# RemoteCar_V1_0.net
KiCad netlist of a schematic drawn in Altium Designer
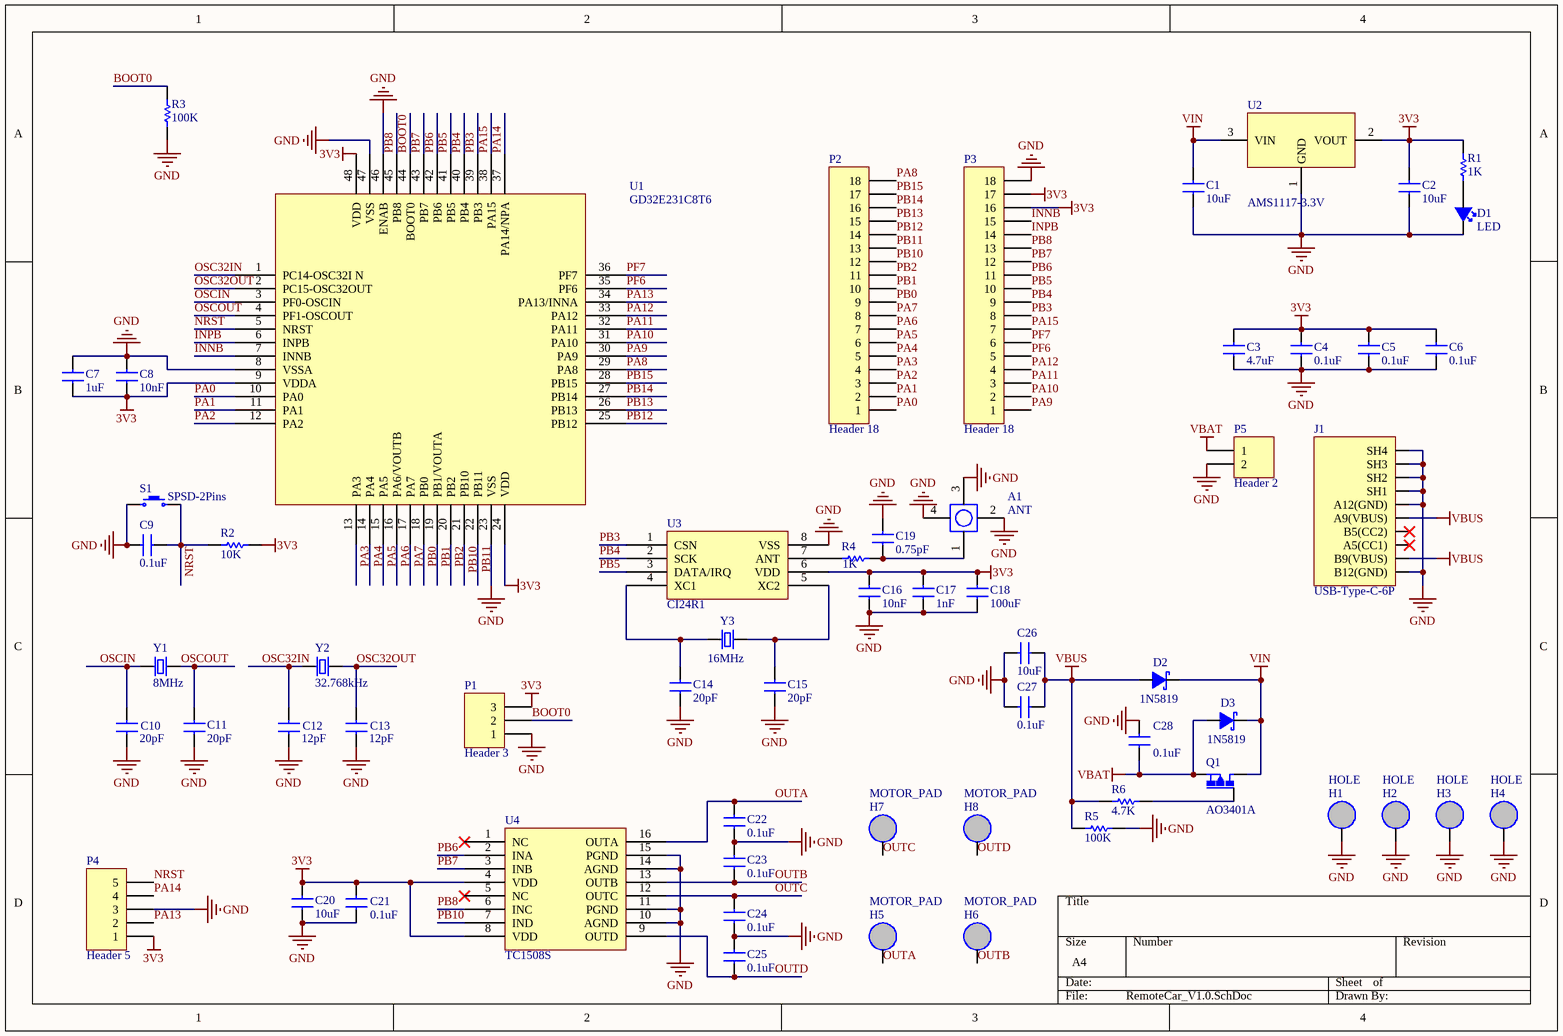
[diagram p0: RemoteCar_V1.0.SchDoc]

(export (version "E")
  (design (tool "Eeschema 10.0.6"))
  (components
    (comp (ref "A1")
      (value "ANT")
      (footprint "RemoteCar_V1.0:IPEX1")
      (libsource (lib "RemoteCar_V1.0") (part "ANT"))
    )
    (comp (ref "C1") (value "10uF") (footprint "CAP-0603") (libsource (lib "GeneralLib") (part "Capacitor")))
    (comp (ref "C2") (value "10uF") (footprint "CAP-0603") (libsource (lib "GeneralLib") (part "Capacitor")))
    (comp (ref "C3") (value "4.7uF") (footprint "CAP-0603") (libsource (lib "GeneralLib") (part "Capacitor")))
    (comp (ref "C4") (value "0.1uF") (footprint "CAP-0402") (libsource (lib "GeneralLib") (part "Capacitor")))
    (comp (ref "C5") (value "0.1uF") (footprint "CAP-0402") (libsource (lib "GeneralLib") (part "Capacitor")))
    (comp (ref "C6") (value "0.1uF") (footprint "CAP-0402") (libsource (lib "GeneralLib") (part "Capacitor")))
    (comp (ref "C7") (value "1uF") (footprint "CAP-0402") (libsource (lib "GeneralLib") (part "Capacitor")))
    (comp (ref "C8") (value "10nF") (footprint "CAP-0402") (libsource (lib "GeneralLib") (part "Capacitor")))
    (comp (ref "C9") (value "0.1uF") (footprint "CAP-0402") (libsource (lib "GeneralLib") (part "Capacitor")))
    (comp (ref "C10") (value "20pF") (footprint "CAP-0603") (libsource (lib "GeneralLib") (part "Capacitor")))
    (comp (ref "C11") (value "20pF") (footprint "CAP-0603") (libsource (lib "GeneralLib") (part "Capacitor")))
    (comp (ref "C12") (value "12pF") (footprint "CAP-0603") (libsource (lib "GeneralLib") (part "Capacitor")))
    (comp (ref "C13") (value "12pF") (footprint "CAP-0603") (libsource (lib "GeneralLib") (part "Capacitor")))
    (comp (ref "C14") (value "20pF") (footprint "CAP-0603") (libsource (lib "GeneralLib") (part "Capacitor")))
    (comp (ref "C15") (value "20pF") (footprint "CAP-0603") (libsource (lib "GeneralLib") (part "Capacitor")))
    (comp (ref "C16") (value "10nF") (footprint "CAP-0402") (libsource (lib "GeneralLib") (part "Capacitor")))
    (comp (ref "C17") (value "1nF") (footprint "CAP-0402") (libsource (lib "GeneralLib") (part "Capacitor")))
    (comp (ref "C18")
      (value "100uF")
      (footprint "CAP-1206")
      (libsource (lib "GeneralLib") (part "Capacitor"))
    )
    (comp (ref "C19")
      (value "0.75pF")
      (footprint "CAP-0402")
      (libsource (lib "GeneralLib") (part "Capacitor"))
    )
    (comp (ref "C20") (value "10uF") (footprint "CAP-0603") (libsource (lib "GeneralLib") (part "Capacitor")))
    (comp (ref "C21")
      (value "0.1uF")
      (footprint "CAP-0402")
      (libsource (lib "GeneralLib") (part "Capacitor"))
    )
    (comp (ref "C22")
      (value "0.1uF")
      (footprint "CAP-0402")
      (libsource (lib "GeneralLib") (part "Capacitor"))
    )
    (comp (ref "C23")
      (value "0.1uF")
      (footprint "CAP-0402")
      (libsource (lib "GeneralLib") (part "Capacitor"))
    )
    (comp (ref "C24")
      (value "0.1uF")
      (footprint "CAP-0402")
      (libsource (lib "GeneralLib") (part "Capacitor"))
    )
    (comp (ref "C25")
      (value "0.1uF")
      (footprint "CAP-0402")
      (libsource (lib "GeneralLib") (part "Capacitor"))
    )
    (comp (ref "C26") (value "10uF") (footprint "CAP-0603") (libsource (lib "GeneralLib") (part "Capacitor")))
    (comp (ref "C27")
      (value "0.1uF")
      (footprint "CAP-0402")
      (libsource (lib "GeneralLib") (part "Capacitor"))
    )
    (comp (ref "C28")
      (value "0.1uF")
      (footprint "CAP-0402")
      (libsource (lib "GeneralLib") (part "Capacitor"))
    )
    (comp (ref "D1") (value "LED") (footprint "LED-0603") (libsource (lib "GeneralLib") (part "LED")))
    (comp (ref "D2")
      (value "1N5819")
      (footprint "GeneralLib:DO-214AC")
      (libsource (lib "GeneralLib") (part "Diode Schottky"))
    )
    (comp (ref "D3")
      (value "1N5819")
      (footprint "GeneralLib:DO-214AC")
      (libsource (lib "GeneralLib") (part "Diode Schottky"))
    )
    (comp (ref "H1")
      (value "HOLE")
      (footprint "RemoteCar_V1.0:HOLE")
      (libsource (lib "RemoteCar_V1.0") (part "HOLE"))
    )
    (comp (ref "H2")
      (value "HOLE")
      (footprint "RemoteCar_V1.0:HOLE")
      (libsource (lib "RemoteCar_V1.0") (part "HOLE"))
    )
    (comp (ref "H3")
      (value "HOLE")
      (footprint "RemoteCar_V1.0:HOLE")
      (libsource (lib "RemoteCar_V1.0") (part "HOLE"))
    )
    (comp (ref "H4")
      (value "HOLE")
      (footprint "RemoteCar_V1.0:HOLE")
      (libsource (lib "RemoteCar_V1.0") (part "HOLE"))
    )
    (comp (ref "H5")
      (value "MOTOR_PAD")
      (footprint "RemoteCar_V1.0:MOTOR_PAD")
      (libsource (lib "RemoteCar_V1.0") (part "MOTOR_PAD"))
    )
    (comp (ref "H6")
      (value "MOTOR_PAD")
      (footprint "RemoteCar_V1.0:MOTOR_PAD")
      (libsource (lib "RemoteCar_V1.0") (part "MOTOR_PAD"))
    )
    (comp (ref "H7")
      (value "MOTOR_PAD")
      (footprint "RemoteCar_V1.0:MOTOR_PAD")
      (libsource (lib "RemoteCar_V1.0") (part "MOTOR_PAD"))
    )
    (comp (ref "H8")
      (value "MOTOR_PAD")
      (footprint "RemoteCar_V1.0:MOTOR_PAD")
      (libsource (lib "RemoteCar_V1.0") (part "MOTOR_PAD"))
    )
    (comp (ref "J1")
      (value "USB-Type-C-6P")
      (footprint "USB-Type-C-6P")
      (libsource (lib "GeneralLib") (part "USB-Type-C-6P"))
    )
    (comp (ref "P1")
      (value "Header 3")
      (footprint "HDR1X3")
      (description "Header, 3-Pin")
      (fields (field (name "PUBLISHER") "Altium Limited"))
      (libsource (lib "Miscellaneous Connectors") (part "Header 3"))
    )
    (comp (ref "P2")
      (value "Header 18")
      (footprint "HDR1X18")
      (description "Header, 18-Pin")
      (fields (field (name "PUBLISHER") "Altium Limited"))
      (libsource (lib "Miscellaneous Connectors") (part "Header 18"))
    )
    (comp (ref "P3")
      (value "Header 18")
      (footprint "HDR1X18")
      (description "Header, 18-Pin")
      (fields (field (name "PUBLISHER") "Altium Limited"))
      (libsource (lib "Miscellaneous Connectors") (part "Header 18"))
    )
    (comp (ref "P4")
      (value "Header 5")
      (footprint "HDR1X5")
      (description "Header, 5-Pin")
      (fields (field (name "PUBLISHER") "Altium Limited"))
      (libsource (lib "Miscellaneous Connectors") (part "Header 5"))
    )
    (comp (ref "P5")
      (value "Header 2")
      (footprint "HDR1X2")
      (description "Header, 2-Pin")
      (fields (field (name "PUBLISHER") "Altium Limited"))
      (libsource (lib "Miscellaneous Connectors") (part "Header 2"))
    )
    (comp (ref "Q1")
      (value "AO3401A")
      (footprint "GeneralLib:SOT95P240X115-3N")
      (libsource (lib "GeneralLib") (part "P-Channel MOSFET"))
    )
    (comp (ref "R1") (value "1K") (footprint "RES-0603") (libsource (lib "GeneralLib") (part "Resistor")))
    (comp (ref "R2") (value "10K") (footprint "RES-0603") (libsource (lib "GeneralLib") (part "Resistor")))
    (comp (ref "R3") (value "100K") (footprint "RES-0603") (libsource (lib "GeneralLib") (part "Resistor")))
    (comp (ref "R4") (value "1K") (footprint "RES-0603") (libsource (lib "GeneralLib") (part "Resistor")))
    (comp (ref "R5") (value "100K") (footprint "RES-0603") (libsource (lib "GeneralLib") (part "Resistor")))
    (comp (ref "R6") (value "4.7K") (footprint "RES-0603") (libsource (lib "GeneralLib") (part "Resistor")))
    (comp (ref "S1")
      (value "SPSD-2Pins")
      (footprint "TS-1101-X-X")
      (libsource (lib "GeneralLib") (part "SPSD 2Pins"))
    )
    (comp (ref "U1")
      (value "GD32E231C8T6")
      (footprint "LQFP-48")
      (libsource (lib "GeneralLib") (part "GD32E231C8T6"))
    )
    (comp (ref "U2")
      (value "AMS1117-3.3V")
      (footprint "RemoteCar_V1.0:SOT230P700X180-4N")
      (libsource (lib "RemoteCar_V1.0") (part "AMS1117-3.3V"))
    )
    (comp (ref "U3")
      (value "CI24R1")
      (footprint "RemoteCar_V1.0:TSOP127P600X145-8N")
      (libsource (lib "RemoteCar_V1.0") (part "CI24R1"))
    )
    (comp (ref "U4")
      (value "TC1508S")
      (footprint "RemoteCar_V1.0:SOP127P600X180-16N")
      (libsource (lib "RemoteCar_V1.0") (part "TC1508S"))
    )
    (comp (ref "Y1") (value "8MHz") (footprint "HC-49S") (libsource (lib "GeneralLib") (part "Crystal 2P")))
    (comp (ref "Y2")
      (value "32.768kHz")
      (footprint "DT-26")
      (libsource (lib "GeneralLib") (part "Crystal 2P"))
    )
    (comp (ref "Y3") (value "16MHz") (footprint "HC-49S") (libsource (lib "GeneralLib") (part "Crystal 2P")))
  )
  (nets
    (net (code "1") (name "/BOOT0") (class "Default")
      (node (ref "P1") (pin "2") (pinfunction "2_2") (pintype "passive"))
      (node (ref "R3") (pin "2") (pinfunction "2_2") (pintype "passive"))
      (node (ref "U1") (pin "44") (pinfunction "BOOT0_44") (pintype "passive"))
    )
    (net (code "2") (name "/INNB") (class "Default")
      (node (ref "P3") (pin "15") (pinfunction "15_15") (pintype "passive"))
      (node (ref "U1") (pin "7") (pinfunction "INNB_7") (pintype "passive"))
    )
    (net (code "3") (name "/INPB") (class "Default")
      (node (ref "P3") (pin "14") (pinfunction "14_14") (pintype "passive"))
      (node (ref "U1") (pin "6") (pinfunction "INPB_6") (pintype "passive"))
    )
    (net (code "4") (name "/NRST") (class "Default")
      (node (ref "C9") (pin "1") (pinfunction "1_1") (pintype "passive"))
      (node (ref "P4") (pin "5") (pinfunction "5_5") (pintype "passive"))
      (node (ref "R2") (pin "1") (pinfunction "1_1") (pintype "passive"))
      (node (ref "S1") (pin "2") (pinfunction "2_2") (pintype "passive"))
      (node (ref "U1") (pin "5") (pinfunction "NRST_5") (pintype "passive"))
    )
    (net (code "5") (name "/OSC32IN") (class "Default")
      (node (ref "C12") (pin "1") (pinfunction "1_1") (pintype "passive"))
      (node (ref "U1") (pin "1") (pinfunction "PC14-OSC32I_N_1") (pintype "passive"))
      (node (ref "Y2") (pin "1") (pinfunction "1_1") (pintype "passive"))
    )
    (net (code "6") (name "/OSC32OUT") (class "Default")
      (node (ref "C13") (pin "1") (pinfunction "1_1") (pintype "passive"))
      (node (ref "U1") (pin "2") (pinfunction "PC15-OSC32OUT_2") (pintype "passive"))
      (node (ref "Y2") (pin "2") (pinfunction "2_2") (pintype "passive"))
    )
    (net (code "7") (name "/OSCIN") (class "Default")
      (node (ref "C10") (pin "1") (pinfunction "1_1") (pintype "passive"))
      (node (ref "U1") (pin "3") (pinfunction "PF0-OSCIN_3") (pintype "passive"))
      (node (ref "Y1") (pin "1") (pinfunction "1_1") (pintype "passive"))
    )
    (net (code "8") (name "/OSCOUT") (class "Default")
      (node (ref "C11") (pin "1") (pinfunction "1_1") (pintype "passive"))
      (node (ref "U1") (pin "4") (pinfunction "PF1-OSCOUT_4") (pintype "passive"))
      (node (ref "Y1") (pin "2") (pinfunction "2_2") (pintype "passive"))
    )
    (net (code "9") (name "/OUTA") (class "Default")
      (node (ref "C22") (pin "2") (pinfunction "2_2") (pintype "passive"))
      (node (ref "H5") (pin "1") (pinfunction "MOTOR_1") (pintype "passive"))
      (node (ref "U4") (pin "16") (pinfunction "OUTA_16") (pintype "passive"))
    )
    (net (code "10") (name "/OUTB") (class "Default")
      (node (ref "C23") (pin "2") (pinfunction "2_2") (pintype "passive"))
      (node (ref "H6") (pin "1") (pinfunction "MOTOR_1") (pintype "passive"))
      (node (ref "U4") (pin "13") (pinfunction "OUTB_13") (pintype "passive"))
    )
    (net (code "11") (name "/OUTC") (class "Default")
      (node (ref "C24") (pin "1") (pinfunction "1_1") (pintype "passive"))
      (node (ref "H7") (pin "1") (pinfunction "MOTOR_1") (pintype "passive"))
      (node (ref "U4") (pin "12") (pinfunction "OUTC_12") (pintype "passive"))
    )
    (net (code "12") (name "/OUTD") (class "Default")
      (node (ref "C25") (pin "2") (pinfunction "2_2") (pintype "passive"))
      (node (ref "H8") (pin "1") (pinfunction "MOTOR_1") (pintype "passive"))
      (node (ref "U4") (pin "9") (pinfunction "OUTD_9") (pintype "passive"))
    )
    (net (code "13") (name "/PA0") (class "Default")
      (node (ref "P2") (pin "1") (pinfunction "1_1") (pintype "passive"))
      (node (ref "U1") (pin "10") (pinfunction "PA0_10") (pintype "passive"))
    )
    (net (code "14") (name "/PA1") (class "Default")
      (node (ref "P2") (pin "2") (pinfunction "2_2") (pintype "passive"))
      (node (ref "U1") (pin "11") (pinfunction "PA1_11") (pintype "passive"))
    )
    (net (code "15") (name "/PA2") (class "Default")
      (node (ref "P2") (pin "3") (pinfunction "3_3") (pintype "passive"))
      (node (ref "U1") (pin "12") (pinfunction "PA2_12") (pintype "passive"))
    )
    (net (code "16") (name "/PA3") (class "Default")
      (node (ref "P2") (pin "4") (pinfunction "4_4") (pintype "passive"))
      (node (ref "U1") (pin "13") (pinfunction "PA3_13") (pintype "passive"))
    )
    (net (code "17") (name "/PA4") (class "Default")
      (node (ref "P2") (pin "5") (pinfunction "5_5") (pintype "passive"))
      (node (ref "U1") (pin "14") (pinfunction "PA4_14") (pintype "passive"))
    )
    (net (code "18") (name "/PA5") (class "Default")
      (node (ref "P2") (pin "6") (pinfunction "6_6") (pintype "passive"))
      (node (ref "U1") (pin "15") (pinfunction "PA5_15") (pintype "passive"))
    )
    (net (code "19") (name "/PA6") (class "Default")
      (node (ref "P2") (pin "7") (pinfunction "7_7") (pintype "passive"))
      (node (ref "U1") (pin "16") (pinfunction "PA6/VOUTB_16") (pintype "passive"))
    )
    (net (code "20") (name "/PA7") (class "Default")
      (node (ref "P2") (pin "8") (pinfunction "8_8") (pintype "passive"))
      (node (ref "U1") (pin "17") (pinfunction "PA7_17") (pintype "passive"))
    )
    (net (code "21") (name "/PA8") (class "Default")
      (node (ref "P2") (pin "18") (pinfunction "18_18") (pintype "passive"))
      (node (ref "U1") (pin "29") (pinfunction "PA8_29") (pintype "passive"))
    )
    (net (code "22") (name "/PA9") (class "Default")
      (node (ref "P3") (pin "1") (pinfunction "1_1") (pintype "passive"))
      (node (ref "U1") (pin "30") (pinfunction "PA9_30") (pintype "passive"))
    )
    (net (code "23") (name "/PA10") (class "Default")
      (node (ref "P3") (pin "2") (pinfunction "2_2") (pintype "passive"))
      (node (ref "U1") (pin "31") (pinfunction "PA10_31") (pintype "passive"))
    )
    (net (code "24") (name "/PA11") (class "Default")
      (node (ref "P3") (pin "3") (pinfunction "3_3") (pintype "passive"))
      (node (ref "U1") (pin "32") (pinfunction "PA11_32") (pintype "passive"))
    )
    (net (code "25") (name "/PA12") (class "Default")
      (node (ref "P3") (pin "4") (pinfunction "4_4") (pintype "passive"))
      (node (ref "U1") (pin "33") (pinfunction "PA12_33") (pintype "passive"))
    )
    (net (code "26") (name "/PA13") (class "Default")
      (node (ref "P4") (pin "2") (pinfunction "2_2") (pintype "passive"))
      (node (ref "U1") (pin "34") (pinfunction "PA13/INNA_34") (pintype "passive"))
    )
    (net (code "27") (name "/PA14") (class "Default")
      (node (ref "P4") (pin "4") (pinfunction "4_4") (pintype "passive"))
      (node (ref "U1") (pin "37") (pinfunction "PA14/NPA_37") (pintype "passive"))
    )
    (net (code "28") (name "/PA15") (class "Default")
      (node (ref "P3") (pin "7") (pinfunction "7_7") (pintype "passive"))
      (node (ref "U1") (pin "38") (pinfunction "PA15_38") (pintype "passive"))
    )
    (net (code "29") (name "/PB0") (class "Default")
      (node (ref "P2") (pin "9") (pinfunction "9_9") (pintype "passive"))
      (node (ref "U1") (pin "18") (pinfunction "PB0_18") (pintype "passive"))
    )
    (net (code "30") (name "/PB1") (class "Default")
      (node (ref "P2") (pin "10") (pinfunction "10_10") (pintype "passive"))
      (node (ref "U1") (pin "19") (pinfunction "PB1/VOUTA_19") (pintype "passive"))
    )
    (net (code "31") (name "/PB2") (class "Default")
      (node (ref "P2") (pin "11") (pinfunction "11_11") (pintype "passive"))
      (node (ref "U1") (pin "20") (pinfunction "PB2_20") (pintype "passive"))
    )
    (net (code "32") (name "/PB3") (class "Default")
      (node (ref "P3") (pin "8") (pinfunction "8_8") (pintype "passive"))
      (node (ref "U1") (pin "39") (pinfunction "PB3_39") (pintype "passive"))
      (node (ref "U3") (pin "1") (pinfunction "CSN_1") (pintype "passive"))
    )
    (net (code "33") (name "/PB4") (class "Default")
      (node (ref "P3") (pin "9") (pinfunction "9_9") (pintype "passive"))
      (node (ref "U1") (pin "40") (pinfunction "PB4_40") (pintype "passive"))
      (node (ref "U3") (pin "2") (pinfunction "SCK_2") (pintype "passive"))
    )
    (net (code "34") (name "/PB5") (class "Default")
      (node (ref "P3") (pin "10") (pinfunction "10_10") (pintype "passive"))
      (node (ref "U1") (pin "41") (pinfunction "PB5_41") (pintype "passive"))
      (node (ref "U3") (pin "3") (pinfunction "DATA/IRQ_3") (pintype "passive"))
    )
    (net (code "35") (name "/PB6") (class "Default")
      (node (ref "P3") (pin "11") (pinfunction "11_11") (pintype "passive"))
      (node (ref "U1") (pin "42") (pinfunction "PB6_42") (pintype "passive"))
      (node (ref "U4") (pin "2") (pinfunction "INA_2") (pintype "passive"))
    )
    (net (code "36") (name "/PB7") (class "Default")
      (node (ref "P3") (pin "12") (pinfunction "12_12") (pintype "passive"))
      (node (ref "U1") (pin "43") (pinfunction "PB7_43") (pintype "passive"))
      (node (ref "U4") (pin "3") (pinfunction "INB_3") (pintype "passive"))
    )
    (net (code "37") (name "/PB8") (class "Default")
      (node (ref "P3") (pin "13") (pinfunction "13_13") (pintype "passive"))
      (node (ref "U1") (pin "45") (pinfunction "PB8_45") (pintype "passive"))
      (node (ref "U4") (pin "6") (pinfunction "INC_6") (pintype "passive"))
    )
    (net (code "38") (name "/PB10") (class "Default")
      (node (ref "P2") (pin "12") (pinfunction "12_12") (pintype "passive"))
      (node (ref "U1") (pin "21") (pinfunction "PB10_21") (pintype "passive"))
      (node (ref "U4") (pin "7") (pinfunction "IND_7") (pintype "passive"))
    )
    (net (code "39") (name "/PB11") (class "Default")
      (node (ref "P2") (pin "13") (pinfunction "13_13") (pintype "passive"))
      (node (ref "U1") (pin "22") (pinfunction "PB11_22") (pintype "passive"))
    )
    (net (code "40") (name "/PB12") (class "Default")
      (node (ref "P2") (pin "14") (pinfunction "14_14") (pintype "passive"))
      (node (ref "U1") (pin "25") (pinfunction "PB12_25") (pintype "passive"))
    )
    (net (code "41") (name "/PB13") (class "Default")
      (node (ref "P2") (pin "15") (pinfunction "15_15") (pintype "passive"))
      (node (ref "U1") (pin "26") (pinfunction "PB13_26") (pintype "passive"))
    )
    (net (code "42") (name "/PB14") (class "Default")
      (node (ref "P2") (pin "16") (pinfunction "16_16") (pintype "passive"))
      (node (ref "U1") (pin "27") (pinfunction "PB14_27") (pintype "passive"))
    )
    (net (code "43") (name "/PB15") (class "Default")
      (node (ref "P2") (pin "17") (pinfunction "17_17") (pintype "passive"))
      (node (ref "U1") (pin "28") (pinfunction "PB15_28") (pintype "passive"))
    )
    (net (code "44") (name "/PF6") (class "Default")
      (node (ref "P3") (pin "5") (pinfunction "5_5") (pintype "passive"))
      (node (ref "U1") (pin "35") (pinfunction "PF6_35") (pintype "passive"))
    )
    (net (code "45") (name "/PF7") (class "Default")
      (node (ref "P3") (pin "6") (pinfunction "6_6") (pintype "passive"))
      (node (ref "U1") (pin "36") (pinfunction "PF7_36") (pintype "passive"))
    )
    (net (code "46") (name "3V3") (class "Default")
      (node (ref "C16") (pin "1") (pinfunction "1_1") (pintype "passive"))
      (node (ref "C17") (pin "1") (pinfunction "1_1") (pintype "passive"))
      (node (ref "C18") (pin "1") (pinfunction "1_1") (pintype "passive"))
      (node (ref "C2") (pin "2") (pinfunction "2_2") (pintype "passive"))
      (node (ref "C20") (pin "1") (pinfunction "1_1") (pintype "passive"))
      (node (ref "C21") (pin "1") (pinfunction "1_1") (pintype "passive"))
      (node (ref "C3") (pin "2") (pinfunction "2_2") (pintype "passive"))
      (node (ref "C4") (pin "2") (pinfunction "2_2") (pintype "passive"))
      (node (ref "C5") (pin "2") (pinfunction "2_2") (pintype "passive"))
      (node (ref "C6") (pin "2") (pinfunction "2_2") (pintype "passive"))
      (node (ref "C7") (pin "1") (pinfunction "1_1") (pintype "passive"))
      (node (ref "C8") (pin "1") (pinfunction "1_1") (pintype "passive"))
      (node (ref "P1") (pin "3") (pinfunction "3_3") (pintype "passive"))
      (node (ref "P3") (pin "16") (pinfunction "16_16") (pintype "passive"))
      (node (ref "P3") (pin "17") (pinfunction "17_17") (pintype "passive"))
      (node (ref "P4") (pin "1") (pinfunction "1_1") (pintype "passive"))
      (node (ref "R1") (pin "2") (pinfunction "2_2") (pintype "passive"))
      (node (ref "R2") (pin "2") (pinfunction "2_2") (pintype "passive"))
      (node (ref "U1") (pin "24") (pinfunction "VDD_24") (pintype "passive"))
      (node (ref "U1") (pin "48") (pinfunction "VDD_48") (pintype "passive"))
      (node (ref "U1") (pin "9") (pinfunction "VDDA_9") (pintype "passive"))
      (node (ref "U2") (pin "2") (pinfunction "VOUT_2") (pintype "passive"))
      (node (ref "U3") (pin "6") (pinfunction "VDD_6") (pintype "passive"))
      (node (ref "U4") (pin "4") (pinfunction "VDD_4") (pintype "passive"))
      (node (ref "U4") (pin "8") (pinfunction "VDD_8") (pintype "passive"))
    )
    (net (code "47") (name "GND") (class "Default")
      (node (ref "A1") (pin "2") (pinfunction "GND_2") (pintype "passive"))
      (node (ref "A1") (pin "3") (pinfunction "GND_3") (pintype "passive"))
      (node (ref "A1") (pin "4") (pinfunction "GND_4") (pintype "passive"))
      (node (ref "C1") (pin "1") (pinfunction "1_1") (pintype "passive"))
      (node (ref "C10") (pin "2") (pinfunction "2_2") (pintype "passive"))
      (node (ref "C11") (pin "2") (pinfunction "2_2") (pintype "passive"))
      (node (ref "C12") (pin "2") (pinfunction "2_2") (pintype "passive"))
      (node (ref "C13") (pin "2") (pinfunction "2_2") (pintype "passive"))
      (node (ref "C14") (pin "2") (pinfunction "2_2") (pintype "passive"))
      (node (ref "C15") (pin "1") (pinfunction "1_1") (pintype "passive"))
      (node (ref "C16") (pin "2") (pinfunction "2_2") (pintype "passive"))
      (node (ref "C17") (pin "2") (pinfunction "2_2") (pintype "passive"))
      (node (ref "C18") (pin "2") (pinfunction "2_2") (pintype "passive"))
      (node (ref "C19") (pin "1") (pinfunction "1_1") (pintype "passive"))
      (node (ref "C2") (pin "1") (pinfunction "1_1") (pintype "passive"))
      (node (ref "C20") (pin "2") (pinfunction "2_2") (pintype "passive"))
      (node (ref "C21") (pin "2") (pinfunction "2_2") (pintype "passive"))
      (node (ref "C22") (pin "1") (pinfunction "1_1") (pintype "passive"))
      (node (ref "C23") (pin "1") (pinfunction "1_1") (pintype "passive"))
      (node (ref "C24") (pin "2") (pinfunction "2_2") (pintype "passive"))
      (node (ref "C25") (pin "1") (pinfunction "1_1") (pintype "passive"))
      (node (ref "C26") (pin "2") (pinfunction "2_2") (pintype "passive"))
      (node (ref "C27") (pin "2") (pinfunction "2_2") (pintype "passive"))
      (node (ref "C28") (pin "2") (pinfunction "2_2") (pintype "passive"))
      (node (ref "C3") (pin "1") (pinfunction "1_1") (pintype "passive"))
      (node (ref "C4") (pin "1") (pinfunction "1_1") (pintype "passive"))
      (node (ref "C5") (pin "1") (pinfunction "1_1") (pintype "passive"))
      (node (ref "C6") (pin "1") (pinfunction "1_1") (pintype "passive"))
      (node (ref "C7") (pin "2") (pinfunction "2_2") (pintype "passive"))
      (node (ref "C8") (pin "2") (pinfunction "2_2") (pintype "passive"))
      (node (ref "C9") (pin "2") (pinfunction "2_2") (pintype "passive"))
      (node (ref "D1") (pin "2") (pinfunction "Cathode_2") (pintype "passive"))
      (node (ref "H1") (pin "1") (pinfunction "GND_1") (pintype "passive"))
      (node (ref "H2") (pin "1") (pinfunction "GND_1") (pintype "passive"))
      (node (ref "H3") (pin "1") (pinfunction "GND_1") (pintype "passive"))
      (node (ref "H4") (pin "1") (pinfunction "GND_1") (pintype "passive"))
      (node (ref "J1") (pin "1") (pinfunction "B12(GND)_1") (pintype "passive"))
      (node (ref "J1") (pin "10") (pinfunction "SH4_10") (pintype "passive"))
      (node (ref "J1") (pin "6") (pinfunction "A12(GND)_6") (pintype "passive"))
      (node (ref "J1") (pin "7") (pinfunction "SH1_7") (pintype "passive"))
      (node (ref "J1") (pin "8") (pinfunction "SH2_8") (pintype "passive"))
      (node (ref "J1") (pin "9") (pinfunction "SH3_9") (pintype "passive"))
      (node (ref "P1") (pin "1") (pinfunction "1_1") (pintype "passive"))
      (node (ref "P3") (pin "18") (pinfunction "18_18") (pintype "passive"))
      (node (ref "P4") (pin "3") (pinfunction "3_3") (pintype "passive"))
      (node (ref "P5") (pin "2") (pinfunction "2_2") (pintype "passive"))
      (node (ref "R3") (pin "1") (pinfunction "1_1") (pintype "passive"))
      (node (ref "R5") (pin "2") (pinfunction "2_2") (pintype "passive"))
      (node (ref "S1") (pin "1") (pinfunction "1_1") (pintype "passive"))
      (node (ref "U1") (pin "23") (pinfunction "VSS_23") (pintype "passive"))
      (node (ref "U1") (pin "46") (pinfunction "ENAB_46") (pintype "passive"))
      (node (ref "U1") (pin "47") (pinfunction "VSS_47") (pintype "passive"))
      (node (ref "U1") (pin "8") (pinfunction "VSSA_8") (pintype "passive"))
      (node (ref "U2") (pin "1") (pinfunction "GND_1") (pintype "passive"))
      (node (ref "U3") (pin "8") (pinfunction "VSS_8") (pintype "passive"))
      (node (ref "U4") (pin "10") (pinfunction "AGND_10") (pintype "passive"))
      (node (ref "U4") (pin "11") (pinfunction "PGND_11") (pintype "passive"))
      (node (ref "U4") (pin "14") (pinfunction "AGND_14") (pintype "passive"))
      (node (ref "U4") (pin "15") (pinfunction "PGND_15") (pintype "passive"))
    )
    (net (code "48") (name "Net-(A1-SIG)") (class "Default")
      (node (ref "A1") (pin "1") (pinfunction "SIG_1") (pintype "passive"))
      (node (ref "C19") (pin "2") (pinfunction "2_2") (pintype "passive"))
      (node (ref "R4") (pin "2") (pinfunction "2_2") (pintype "passive"))
    )
    (net (code "49") (name "Net-(D1-Positive)") (class "Default")
      (node (ref "D1") (pin "1") (pinfunction "Positive_1") (pintype "passive"))
      (node (ref "R1") (pin "1") (pinfunction "1_1") (pintype "passive"))
    )
    (net (code "50") (name "Net-(Q1-G)") (class "Default")
      (node (ref "Q1") (pin "1") (pinfunction "G_1") (pintype "passive"))
      (node (ref "R6") (pin "2") (pinfunction "2_2") (pintype "passive"))
    )
    (net (code "51") (name "Net-(U3-ANT)") (class "Default")
      (node (ref "R4") (pin "1") (pinfunction "1_1") (pintype "passive"))
      (node (ref "U3") (pin "7") (pinfunction "ANT_7") (pintype "passive"))
    )
    (net (code "52") (name "Net-(U3-XC1)") (class "Default")
      (node (ref "C14") (pin "1") (pinfunction "1_1") (pintype "passive"))
      (node (ref "U3") (pin "4") (pinfunction "XC1_4") (pintype "passive"))
      (node (ref "Y3") (pin "1") (pinfunction "1_1") (pintype "passive"))
    )
    (net (code "53") (name "Net-(U3-XC2)") (class "Default")
      (node (ref "C15") (pin "2") (pinfunction "2_2") (pintype "passive"))
      (node (ref "U3") (pin "5") (pinfunction "XC2_5") (pintype "passive"))
      (node (ref "Y3") (pin "2") (pinfunction "2_2") (pintype "passive"))
    )
    (net (code "54") (name "VBAT") (class "Default")
      (node (ref "C28") (pin "1") (pinfunction "1_1") (pintype "passive"))
      (node (ref "D3") (pin "1") (pinfunction "Positive_1") (pintype "passive"))
      (node (ref "P5") (pin "1") (pinfunction "1_1") (pintype "passive"))
      (node (ref "Q1") (pin "2") (pinfunction "S_2") (pintype "passive"))
    )
    (net (code "55") (name "VBUS") (class "Default")
      (node (ref "C26") (pin "1") (pinfunction "1_1") (pintype "passive"))
      (node (ref "C27") (pin "1") (pinfunction "1_1") (pintype "passive"))
      (node (ref "D2") (pin "1") (pinfunction "Positive_1") (pintype "passive"))
      (node (ref "J1") (pin "2") (pinfunction "B9(VBUS)_2") (pintype "passive"))
      (node (ref "J1") (pin "5") (pinfunction "A9(VBUS)_5") (pintype "passive"))
      (node (ref "R5") (pin "1") (pinfunction "1_1") (pintype "passive"))
      (node (ref "R6") (pin "1") (pinfunction "1_1") (pintype "passive"))
    )
    (net (code "56") (name "VIN") (class "Default")
      (node (ref "C1") (pin "2") (pinfunction "2_2") (pintype "passive"))
      (node (ref "D2") (pin "2") (pinfunction "Cathode_2") (pintype "passive"))
      (node (ref "D3") (pin "2") (pinfunction "Cathode_2") (pintype "passive"))
      (node (ref "Q1") (pin "3") (pinfunction "D_3") (pintype "passive"))
      (node (ref "U2") (pin "3") (pinfunction "VIN_3") (pintype "passive"))
    )
    (net (code "57") (name "unconnected-(J1-A5(CC1)-Pad3)") (class "Default")
      (node (ref "J1") (pin "3") (pinfunction "A5(CC1)_3") (pintype "passive+no_connect"))
    )
    (net (code "58") (name "unconnected-(J1-B5(CC2)-Pad4)") (class "Default")
      (node (ref "J1") (pin "4") (pinfunction "B5(CC2)_4") (pintype "passive+no_connect"))
    )
    (net (code "59") (name "unconnected-(U4-NC-Pad1)") (class "Default")
      (node (ref "U4") (pin "1") (pinfunction "NC_1") (pintype "passive+no_connect"))
    )
    (net (code "60") (name "unconnected-(U4-NC-Pad5)") (class "Default")
      (node (ref "U4") (pin "5") (pinfunction "NC_5") (pintype "passive+no_connect"))
    )
  )
)
